# 702_MAX6675_solder_station_v1.net
KiCad netlist of a schematic drawn in EAGLE
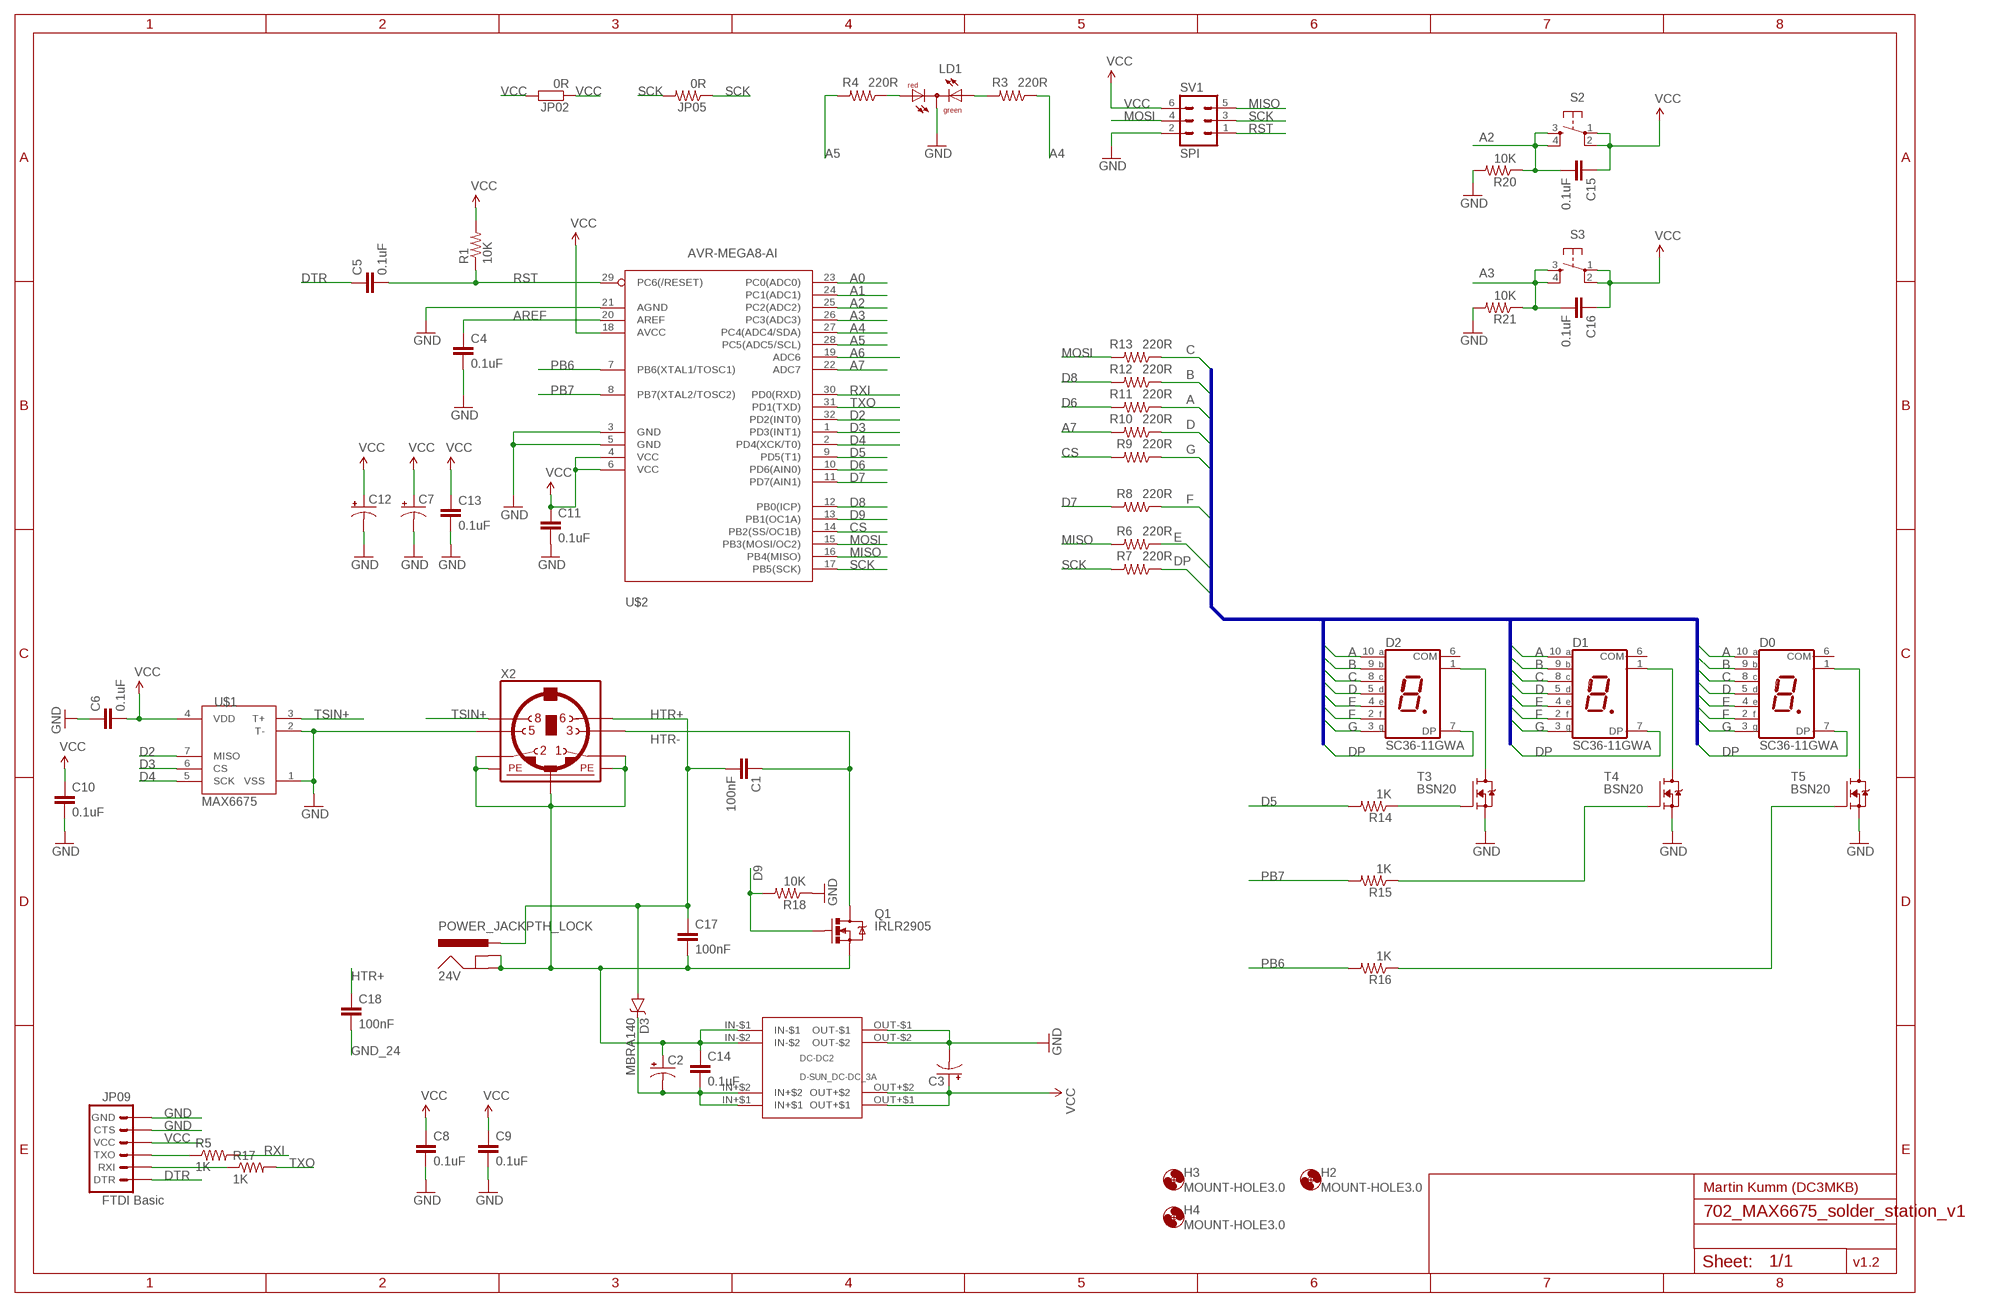
[diagram p0: schematic, sheet 1]

(export (version "E")
  (design (tool "Eeschema 10.0.6"))
  (components
    (comp (ref "24V")
      (value "POWER_JACKPTH_LOCK")
      (footprint "eagle-import:POWER_JACK_PTH_LOCK")
      (libsource (lib "eagle-import") (part "POWER_JACKPTH_LOCK"))
    )
    (comp (ref "C1")
      (value "100nF")
      (footprint "eagle-import:1206")
      (libsource (lib "eagle-import") (part "SparkFun-Passives_CAP1206"))
    )
    (comp (ref "C2")
      (value "CAP_POLPTH1")
      (footprint "eagle-import:CPOL-RADIAL-100UF-25V")
      (libsource (lib "eagle-import") (part "SparkFun-Passives_CAP_POLPTH1"))
    )
    (comp (ref "C3")
      (value "CAP_POLPTH1")
      (footprint "eagle-import:CPOL-RADIAL-100UF-25V")
      (libsource (lib "eagle-import") (part "SparkFun-Passives_CAP_POLPTH1"))
    )
    (comp (ref "C4")
      (value "0.1uF")
      (footprint "eagle-import:0805")
      (libsource (lib "eagle-import") (part "CAP0805"))
    )
    (comp (ref "C5")
      (value "0.1uF")
      (footprint "eagle-import:0805")
      (libsource (lib "eagle-import") (part "CAP0805"))
    )
    (comp (ref "C6")
      (value "0.1uF")
      (footprint "eagle-import:0805")
      (libsource (lib "eagle-import") (part "CAP0805"))
    )
    (comp (ref "C7")
      (value "CAP_POL1206")
      (footprint "eagle-import:EIA3216")
      (libsource (lib "eagle-import") (part "CAP_POL1206"))
    )
    (comp (ref "C8")
      (value "0.1uF")
      (footprint "eagle-import:0805")
      (libsource (lib "eagle-import") (part "CAP0805"))
    )
    (comp (ref "C9")
      (value "0.1uF")
      (footprint "eagle-import:0805")
      (libsource (lib "eagle-import") (part "CAP0805"))
    )
    (comp (ref "C10")
      (value "0.1uF")
      (footprint "eagle-import:0805")
      (libsource (lib "eagle-import") (part "CAP0805"))
    )
    (comp (ref "C11")
      (value "0.1uF")
      (footprint "eagle-import:0805")
      (libsource (lib "eagle-import") (part "CAP0805"))
    )
    (comp (ref "C12")
      (value "CAP_POL1206")
      (footprint "eagle-import:EIA3216")
      (libsource (lib "eagle-import") (part "CAP_POL1206"))
    )
    (comp (ref "C13")
      (value "0.1uF")
      (footprint "eagle-import:0805")
      (libsource (lib "eagle-import") (part "CAP0805"))
    )
    (comp (ref "C14")
      (value "0.1uF")
      (footprint "eagle-import:1206")
      (libsource (lib "eagle-import") (part "CAP1206"))
    )
    (comp (ref "C15")
      (value "0.1uF")
      (footprint "eagle-import:0805")
      (libsource (lib "eagle-import") (part "CAP0805"))
    )
    (comp (ref "C16")
      (value "0.1uF")
      (footprint "eagle-import:0805")
      (libsource (lib "eagle-import") (part "CAP0805"))
    )
    (comp (ref "C17")
      (value "100nF")
      (footprint "eagle-import:1206")
      (libsource (lib "eagle-import") (part "SparkFun-Passives_CAP1206"))
    )
    (comp (ref "C18")
      (value "100nF")
      (footprint "eagle-import:1206")
      (libsource (lib "eagle-import") (part "SparkFun-Passives_CAP1206"))
    )
    (comp (ref "D0")
      (value "SC36-11GWA")
      (footprint "eagle-import:SA36-11GWA")
      (libsource (lib "eagle-import") (part "SA36-11GWA"))
    )
    (comp (ref "D1")
      (value "SC36-11GWA")
      (footprint "eagle-import:SA36-11GWA")
      (libsource (lib "eagle-import") (part "SA36-11GWA"))
    )
    (comp (ref "D2")
      (value "SC36-11GWA")
      (footprint "eagle-import:SA36-11GWA")
      (libsource (lib "eagle-import") (part "SA36-11GWA"))
    )
    (comp (ref "D3")
      (value "MBRA140")
      (footprint "eagle-import:SMA-DIODE")
      (libsource (lib "eagle-import") (part "MBRA140"))
    )
    (comp (ref "DC-DC2")
      (value "D-SUN_DC-DC_3A")
      (footprint "eagle-import:D-SUN_DC-DC_3A")
      (libsource (lib "eagle-import") (part "D-SUN_DC-DC_3A"))
    )
    (comp (ref "H2")
      (value "MOUNT-HOLE3.0")
      (footprint "eagle-import:3,0")
      (libsource (lib "eagle-import") (part "MOUNT-HOLE3.0"))
    )
    (comp (ref "H3")
      (value "MOUNT-HOLE3.0")
      (footprint "eagle-import:3,0")
      (libsource (lib "eagle-import") (part "MOUNT-HOLE3.0"))
    )
    (comp (ref "H4")
      (value "MOUNT-HOLE3.0")
      (footprint "eagle-import:3,0")
      (libsource (lib "eagle-import") (part "MOUNT-HOLE3.0"))
    )
    (comp (ref "JP02")
      (value "0R")
      (footprint "eagle-import:R1206")
      (libsource (lib "eagle-import") (part "R-EU_R1206"))
    )
    (comp (ref "JP05")
      (value "0R")
      (footprint "eagle-import:0805")
      (libsource (lib "eagle-import") (part "RESISTOR0805-RES"))
    )
    (comp (ref "JP09")
      (value "FTDI Basic")
      (footprint "eagle-import:1X06")
      (libsource (lib "eagle-import") (part "ARDUINO_SERIAL_PROGRAMPTH"))
    )
    (comp (ref "LD1")
      (value "DUOLED-RG-C")
      (footprint "eagle-import:DUOLED-C-5MM")
      (libsource (lib "eagle-import") (part "DUOLED-RG-C"))
    )
    (comp (ref "Q1")
      (value "IRLR2905")
      (footprint "eagle-import:DPAK")
      (libsource (lib "eagle-import") (part "MOSFET-NCHANNELFDD8780"))
    )
    (comp (ref "R1")
      (value "10K")
      (footprint "eagle-import:0805")
      (libsource (lib "eagle-import") (part "RESISTOR0805-RES"))
    )
    (comp (ref "R3")
      (value "220R")
      (footprint "eagle-import:0805")
      (libsource (lib "eagle-import") (part "RESISTOR0805-RES"))
    )
    (comp (ref "R4")
      (value "220R")
      (footprint "eagle-import:0805")
      (libsource (lib "eagle-import") (part "RESISTOR0805-RES"))
    )
    (comp (ref "R5")
      (value "1K")
      (footprint "eagle-import:0805")
      (libsource (lib "eagle-import") (part "RESISTOR0805-RES"))
    )
    (comp (ref "R6")
      (value "220R")
      (footprint "eagle-import:0805")
      (libsource (lib "eagle-import") (part "RESISTOR0805-RES"))
    )
    (comp (ref "R7")
      (value "220R")
      (footprint "eagle-import:0805")
      (libsource (lib "eagle-import") (part "RESISTOR0805-RES"))
    )
    (comp (ref "R8")
      (value "220R")
      (footprint "eagle-import:0805")
      (libsource (lib "eagle-import") (part "RESISTOR0805-RES"))
    )
    (comp (ref "R9")
      (value "220R")
      (footprint "eagle-import:0805")
      (libsource (lib "eagle-import") (part "RESISTOR0805-RES"))
    )
    (comp (ref "R10")
      (value "220R")
      (footprint "eagle-import:0805")
      (libsource (lib "eagle-import") (part "RESISTOR0805-RES"))
    )
    (comp (ref "R11")
      (value "220R")
      (footprint "eagle-import:0805")
      (libsource (lib "eagle-import") (part "RESISTOR0805-RES"))
    )
    (comp (ref "R12")
      (value "220R")
      (footprint "eagle-import:0805")
      (libsource (lib "eagle-import") (part "RESISTOR0805-RES"))
    )
    (comp (ref "R13")
      (value "220R")
      (footprint "eagle-import:0805")
      (libsource (lib "eagle-import") (part "RESISTOR0805-RES"))
    )
    (comp (ref "R14")
      (value "1K")
      (footprint "eagle-import:0805")
      (libsource (lib "eagle-import") (part "RESISTOR0805-RES"))
    )
    (comp (ref "R15")
      (value "1K")
      (footprint "eagle-import:0805")
      (libsource (lib "eagle-import") (part "RESISTOR0805-RES"))
    )
    (comp (ref "R16")
      (value "1K")
      (footprint "eagle-import:0805")
      (libsource (lib "eagle-import") (part "RESISTOR0805-RES"))
    )
    (comp (ref "R17")
      (value "1K")
      (footprint "eagle-import:0805")
      (libsource (lib "eagle-import") (part "RESISTOR0805-RES"))
    )
    (comp (ref "R18")
      (value "10K")
      (footprint "eagle-import:0805")
      (libsource (lib "eagle-import") (part "RESISTOR0805-RES"))
    )
    (comp (ref "R20")
      (value "10K")
      (footprint "eagle-import:0805")
      (libsource (lib "eagle-import") (part "RESISTOR0805-RES"))
    )
    (comp (ref "R21")
      (value "10K")
      (footprint "eagle-import:0805")
      (libsource (lib "eagle-import") (part "RESISTOR0805-RES"))
    )
    (comp (ref "S2")
      (value "TAC_SWITCHPTH")
      (footprint "eagle-import:TACTILE-PTH")
      (libsource (lib "eagle-import") (part "TAC_SWITCHPTH"))
    )
    (comp (ref "S3")
      (value "TAC_SWITCHPTH")
      (footprint "eagle-import:TACTILE-PTH")
      (libsource (lib "eagle-import") (part "TAC_SWITCHPTH"))
    )
    (comp (ref "SV1")
      (value "SPI")
      (footprint "eagle-import:ML6")
      (libsource (lib "eagle-import") (part "ML6"))
    )
    (comp (ref "T3")
      (value "BSN20")
      (footprint "eagle-import:SOT23")
      (libsource (lib "eagle-import") (part "BSN20"))
    )
    (comp (ref "T4")
      (value "BSN20")
      (footprint "eagle-import:SOT23")
      (libsource (lib "eagle-import") (part "BSN20"))
    )
    (comp (ref "T5")
      (value "BSN20")
      (footprint "eagle-import:SOT23")
      (libsource (lib "eagle-import") (part "BSN20"))
    )
    (comp (ref "U$1")
      (value "MAX6675")
      (footprint "eagle-import:SO08-MAX6675")
      (libsource (lib "eagle-import") (part "MAX6675"))
    )
    (comp (ref "U$2")
      (value "AVR-MEGA8-AI")
      (footprint "eagle-import:TQFP32-08")
      (libsource (lib "eagle-import") (part "AVR-MEGA8-AI"))
    )
    (comp (ref "X2")
      (value "MINI_DIN_6")
      (footprint "eagle-import:M_DIN6")
      (libsource (lib "eagle-import") (part "MINI_DIN_6"))
    )
  )
  (nets
    (net (code "1") (name "/A") (class "Default")
      (node (ref "D0") (pin "10") (pinfunction "A_10") (pintype "passive"))
      (node (ref "D1") (pin "10") (pinfunction "A_10") (pintype "passive"))
      (node (ref "D2") (pin "10") (pinfunction "A_10") (pintype "passive"))
      (node (ref "R11") (pin "1") (pinfunction "1_1") (pintype "passive"))
    )
    (net (code "2") (name "/A0") (class "Default")
      (node (ref "U$2") (pin "23") (pinfunction "PC0(ADC0)_23") (pintype "bidirectional"))
    )
    (net (code "3") (name "/A1") (class "Default")
      (node (ref "U$2") (pin "24") (pinfunction "PC1(ADC1)_24") (pintype "bidirectional"))
    )
    (net (code "4") (name "/A2") (class "Default")
      (node (ref "C15") (pin "2") (pinfunction "2_2") (pintype "passive"))
      (node (ref "R20") (pin "1") (pinfunction "1_1") (pintype "passive"))
      (node (ref "S2") (pin "3") (pinfunction "3_3") (pintype "passive"))
      (node (ref "S2") (pin "4") (pinfunction "4_4") (pintype "passive"))
      (node (ref "U$2") (pin "25") (pinfunction "PC2(ADC2)_25") (pintype "bidirectional"))
    )
    (net (code "5") (name "/A3") (class "Default")
      (node (ref "C16") (pin "2") (pinfunction "2_2") (pintype "passive"))
      (node (ref "R21") (pin "1") (pinfunction "1_1") (pintype "passive"))
      (node (ref "S3") (pin "3") (pinfunction "3_3") (pintype "passive"))
      (node (ref "S3") (pin "4") (pinfunction "4_4") (pintype "passive"))
      (node (ref "U$2") (pin "26") (pinfunction "PC3(ADC3)_26") (pintype "bidirectional"))
    )
    (net (code "6") (name "/A4") (class "Default")
      (node (ref "R3") (pin "1") (pinfunction "1_1") (pintype "passive"))
      (node (ref "U$2") (pin "27") (pinfunction "PC4(ADC4/SDA)_27") (pintype "bidirectional"))
    )
    (net (code "7") (name "/A5") (class "Default")
      (node (ref "R4") (pin "2") (pinfunction "2_2") (pintype "passive"))
      (node (ref "U$2") (pin "28") (pinfunction "PC5(ADC5/SCL)_28") (pintype "bidirectional"))
    )
    (net (code "8") (name "/A6") (class "Default")
      (node (ref "U$2") (pin "19") (pinfunction "ADC6_19") (pintype "bidirectional"))
    )
    (net (code "9") (name "/A7") (class "Default")
      (node (ref "R10") (pin "2") (pinfunction "2_2") (pintype "passive"))
      (node (ref "U$2") (pin "22") (pinfunction "ADC7_22") (pintype "bidirectional"))
    )
    (net (code "10") (name "/AREF") (class "Default")
      (node (ref "C4") (pin "1") (pinfunction "1_1") (pintype "passive"))
      (node (ref "U$2") (pin "20") (pinfunction "AREF_20") (pintype "bidirectional"))
    )
    (net (code "11") (name "/B") (class "Default")
      (node (ref "D0") (pin "9") (pinfunction "B_9") (pintype "passive"))
      (node (ref "D1") (pin "9") (pinfunction "B_9") (pintype "passive"))
      (node (ref "D2") (pin "9") (pinfunction "B_9") (pintype "passive"))
      (node (ref "R12") (pin "1") (pinfunction "1_1") (pintype "passive"))
    )
    (net (code "12") (name "/C") (class "Default")
      (node (ref "D0") (pin "8") (pinfunction "C_8") (pintype "passive"))
      (node (ref "D1") (pin "8") (pinfunction "C_8") (pintype "passive"))
      (node (ref "D2") (pin "8") (pinfunction "C_8") (pintype "passive"))
      (node (ref "R13") (pin "1") (pinfunction "1_1") (pintype "passive"))
    )
    (net (code "13") (name "/CS") (class "Default")
      (node (ref "R9") (pin "2") (pinfunction "2_2") (pintype "passive"))
      (node (ref "U$2") (pin "14") (pinfunction "PB2(SS/OC1B)_14") (pintype "bidirectional"))
    )
    (net (code "14") (name "/D") (class "Default")
      (node (ref "D0") (pin "5") (pinfunction "D_5") (pintype "passive"))
      (node (ref "D1") (pin "5") (pinfunction "D_5") (pintype "passive"))
      (node (ref "D2") (pin "5") (pinfunction "D_5") (pintype "passive"))
      (node (ref "R10") (pin "1") (pinfunction "1_1") (pintype "passive"))
    )
    (net (code "15") (name "/D2") (class "Default")
      (node (ref "U$1") (pin "7") (pinfunction "MISO_7") (pintype "bidirectional"))
      (node (ref "U$2") (pin "32") (pinfunction "PD2(INT0)_32") (pintype "bidirectional"))
    )
    (net (code "16") (name "/D3") (class "Default")
      (node (ref "U$1") (pin "6") (pinfunction "CS_6") (pintype "bidirectional"))
      (node (ref "U$2") (pin "1") (pinfunction "PD3(INT1)_1") (pintype "bidirectional"))
    )
    (net (code "17") (name "/D4") (class "Default")
      (node (ref "U$1") (pin "5") (pinfunction "SCK_5") (pintype "bidirectional"))
      (node (ref "U$2") (pin "2") (pinfunction "PD4(XCK/T0)_2") (pintype "bidirectional"))
    )
    (net (code "18") (name "/D5") (class "Default")
      (node (ref "R14") (pin "2") (pinfunction "2_2") (pintype "passive"))
      (node (ref "U$2") (pin "9") (pinfunction "PD5(T1)_9") (pintype "bidirectional"))
    )
    (net (code "19") (name "/D6") (class "Default")
      (node (ref "R11") (pin "2") (pinfunction "2_2") (pintype "passive"))
      (node (ref "U$2") (pin "10") (pinfunction "PD6(AIN0)_10") (pintype "bidirectional"))
    )
    (net (code "20") (name "/D7") (class "Default")
      (node (ref "R8") (pin "2") (pinfunction "2_2") (pintype "passive"))
      (node (ref "U$2") (pin "11") (pinfunction "PD7(AIN1)_11") (pintype "bidirectional"))
    )
    (net (code "21") (name "/D8") (class "Default")
      (node (ref "R12") (pin "2") (pinfunction "2_2") (pintype "passive"))
      (node (ref "U$2") (pin "12") (pinfunction "PB0(ICP)_12") (pintype "bidirectional"))
    )
    (net (code "22") (name "/D9") (class "Default")
      (node (ref "Q1") (pin "1") (pinfunction "G_1") (pintype "passive"))
      (node (ref "R18") (pin "2") (pinfunction "2_2") (pintype "passive"))
      (node (ref "U$2") (pin "13") (pinfunction "PB1(OC1A)_13") (pintype "bidirectional"))
    )
    (net (code "23") (name "/DP") (class "Default")
      (node (ref "D0") (pin "7") (pinfunction "DP_7") (pintype "passive"))
      (node (ref "D1") (pin "7") (pinfunction "DP_7") (pintype "passive"))
      (node (ref "D2") (pin "7") (pinfunction "DP_7") (pintype "passive"))
      (node (ref "R7") (pin "1") (pinfunction "1_1") (pintype "passive"))
    )
    (net (code "24") (name "/DTR") (class "Default")
      (node (ref "C5") (pin "1") (pinfunction "1_1") (pintype "passive"))
      (node (ref "JP09") (pin "1") (pinfunction "DTR_1") (pintype "passive"))
    )
    (net (code "25") (name "/E") (class "Default")
      (node (ref "D0") (pin "4") (pinfunction "E_4") (pintype "passive"))
      (node (ref "D1") (pin "4") (pinfunction "E_4") (pintype "passive"))
      (node (ref "D2") (pin "4") (pinfunction "E_4") (pintype "passive"))
      (node (ref "R6") (pin "1") (pinfunction "1_1") (pintype "passive"))
    )
    (net (code "26") (name "/F") (class "Default")
      (node (ref "D0") (pin "2") (pinfunction "F_2") (pintype "passive"))
      (node (ref "D1") (pin "2") (pinfunction "F_2") (pintype "passive"))
      (node (ref "D2") (pin "2") (pinfunction "F_2") (pintype "passive"))
      (node (ref "R8") (pin "1") (pinfunction "1_1") (pintype "passive"))
    )
    (net (code "27") (name "/G") (class "Default")
      (node (ref "D0") (pin "3") (pinfunction "G_3") (pintype "passive"))
      (node (ref "D1") (pin "3") (pinfunction "G_3") (pintype "passive"))
      (node (ref "D2") (pin "3") (pinfunction "G_3") (pintype "passive"))
      (node (ref "R9") (pin "1") (pinfunction "1_1") (pintype "passive"))
    )
    (net (code "28") (name "/GND_24") (class "Default")
      (node (ref "24V") (pin "GND") (pinfunction "GND_GND") (pintype "bidirectional"))
      (node (ref "24V") (pin "GNDBREAK") (pinfunction "GNDBREAK_GNDBREAK") (pintype "bidirectional"))
      (node (ref "C14") (pin "1") (pinfunction "1_1") (pintype "passive"))
      (node (ref "C17") (pin "2") (pinfunction "2_2") (pintype "passive"))
      (node (ref "C18") (pin "2") (pinfunction "2_2") (pintype "passive"))
      (node (ref "C2") (pin "1") (pinfunction "+_1") (pintype "passive"))
      (node (ref "DC-DC2") (pin "IN-$1") (pinfunction "IN-$1_IN-$1") (pintype "power_in"))
      (node (ref "DC-DC2") (pin "IN-$2") (pinfunction "IN-$2_IN-$2") (pintype "power_in"))
      (node (ref "Q1") (pin "3") (pinfunction "S_3") (pintype "passive"))
      (node (ref "X2") (pin "1") (pinfunction "1_1") (pintype "passive"))
      (node (ref "X2") (pin "2") (pinfunction "2_2") (pintype "passive"))
      (node (ref "X2") (pin "SH1") (pinfunction "PE1_SH1") (pintype "power_in"))
      (node (ref "X2") (pin "SH2") (pinfunction "PE2_SH2") (pintype "power_in"))
      (node (ref "X2") (pin "SH3") (pinfunction "PE3_SH3") (pintype "power_in"))
    )
    (net (code "29") (name "/HTR+") (class "Default")
      (node (ref "24V") (pin "PWR") (pinfunction "PWR_PWR") (pintype "bidirectional"))
      (node (ref "C1") (pin "2") (pinfunction "2_2") (pintype "passive"))
      (node (ref "C17") (pin "1") (pinfunction "1_1") (pintype "passive"))
      (node (ref "C18") (pin "1") (pinfunction "1_1") (pintype "passive"))
      (node (ref "D3") (pin "A") (pinfunction "A_A") (pintype "passive"))
      (node (ref "X2") (pin "6") (pinfunction "6_6") (pintype "passive"))
    )
    (net (code "30") (name "/HTR-") (class "Default")
      (node (ref "C1") (pin "1") (pinfunction "1_1") (pintype "passive"))
      (node (ref "Q1") (pin "4") (pinfunction "D_4") (pintype "passive"))
      (node (ref "X2") (pin "3") (pinfunction "3_3") (pintype "passive"))
    )
    (net (code "31") (name "/MISO") (class "Default")
      (node (ref "R6") (pin "2") (pinfunction "2_2") (pintype "passive"))
      (node (ref "SV1") (pin "5") (pinfunction "5_5") (pintype "passive"))
      (node (ref "U$2") (pin "16") (pinfunction "PB4(MISO)_16") (pintype "bidirectional"))
    )
    (net (code "32") (name "/MOSI") (class "Default")
      (node (ref "R13") (pin "2") (pinfunction "2_2") (pintype "passive"))
      (node (ref "SV1") (pin "4") (pinfunction "4_4") (pintype "passive"))
      (node (ref "U$2") (pin "15") (pinfunction "PB3(MOSI/OC2)_15") (pintype "bidirectional"))
    )
    (net (code "33") (name "/PB6") (class "Default")
      (node (ref "R16") (pin "2") (pinfunction "2_2") (pintype "passive"))
      (node (ref "U$2") (pin "7") (pinfunction "PB6(XTAL1/TOSC1)_7") (pintype "bidirectional"))
    )
    (net (code "34") (name "/PB7") (class "Default")
      (node (ref "R15") (pin "2") (pinfunction "2_2") (pintype "passive"))
      (node (ref "U$2") (pin "8") (pinfunction "PB7(XTAL2/TOSC2)_8") (pintype "bidirectional"))
    )
    (net (code "35") (name "/RST") (class "Default")
      (node (ref "C5") (pin "2") (pinfunction "2_2") (pintype "passive"))
      (node (ref "R1") (pin "1") (pinfunction "1_1") (pintype "passive"))
      (node (ref "SV1") (pin "1") (pinfunction "1_1") (pintype "passive"))
      (node (ref "U$2") (pin "29") (pinfunction "PC6(/RESET)_29") (pintype "bidirectional"))
    )
    (net (code "36") (name "/RXI") (class "Default")
      (node (ref "R5") (pin "2") (pinfunction "2_2") (pintype "passive"))
      (node (ref "U$2") (pin "30") (pinfunction "PD0(RXD)_30") (pintype "bidirectional"))
    )
    (net (code "37") (name "/SCK") (class "Default")
      (node (ref "JP05") (pin "1") (pinfunction "1_1") (pintype "passive"))
      (node (ref "JP05") (pin "2") (pinfunction "2_2") (pintype "passive"))
      (node (ref "R7") (pin "2") (pinfunction "2_2") (pintype "passive"))
      (node (ref "SV1") (pin "3") (pinfunction "3_3") (pintype "passive"))
      (node (ref "U$2") (pin "17") (pinfunction "PB5(SCK)_17") (pintype "bidirectional"))
    )
    (net (code "38") (name "/TSIN+") (class "Default")
      (node (ref "U$1") (pin "3") (pinfunction "T+_3") (pintype "bidirectional"))
      (node (ref "X2") (pin "8") (pinfunction "8_8") (pintype "passive"))
    )
    (net (code "39") (name "/TXO") (class "Default")
      (node (ref "R17") (pin "2") (pinfunction "2_2") (pintype "passive"))
      (node (ref "U$2") (pin "31") (pinfunction "PD1(TXD)_31") (pintype "bidirectional"))
    )
    (net (code "41") (name "GND") (class "Default")
      (node (ref "C10") (pin "2") (pinfunction "2_2") (pintype "passive"))
      (node (ref "C11") (pin "2") (pinfunction "2_2") (pintype "passive"))
      (node (ref "C12") (pin "C") (pinfunction "-_C") (pintype "passive"))
      (node (ref "C13") (pin "2") (pinfunction "2_2") (pintype "passive"))
      (node (ref "C3") (pin "2") (pinfunction "-_2") (pintype "passive"))
      (node (ref "C4") (pin "2") (pinfunction "2_2") (pintype "passive"))
      (node (ref "C6") (pin "1") (pinfunction "1_1") (pintype "passive"))
      (node (ref "C7") (pin "C") (pinfunction "-_C") (pintype "passive"))
      (node (ref "C8") (pin "2") (pinfunction "2_2") (pintype "passive"))
      (node (ref "C9") (pin "2") (pinfunction "2_2") (pintype "passive"))
      (node (ref "DC-DC2") (pin "OUT-$1") (pinfunction "OUT-$1_OUT-$1") (pintype "power_in"))
      (node (ref "DC-DC2") (pin "OUT-$2") (pinfunction "OUT-$2_OUT-$2") (pintype "power_in"))
      (node (ref "JP09") (pin "5") (pinfunction "CTS_5") (pintype "passive"))
      (node (ref "JP09") (pin "6") (pinfunction "GND_6") (pintype "passive"))
      (node (ref "LD1") (pin "C") (pinfunction "C_C") (pintype "passive"))
      (node (ref "R18") (pin "1") (pinfunction "1_1") (pintype "passive"))
      (node (ref "R20") (pin "2") (pinfunction "2_2") (pintype "passive"))
      (node (ref "R21") (pin "2") (pinfunction "2_2") (pintype "passive"))
      (node (ref "SV1") (pin "2") (pinfunction "2_2") (pintype "passive"))
      (node (ref "T3") (pin "2") (pinfunction "S_2") (pintype "passive"))
      (node (ref "T4") (pin "2") (pinfunction "S_2") (pintype "passive"))
      (node (ref "T5") (pin "2") (pinfunction "S_2") (pintype "passive"))
      (node (ref "U$1") (pin "1") (pinfunction "VSS_1") (pintype "bidirectional"))
      (node (ref "U$1") (pin "2") (pinfunction "T-_2") (pintype "bidirectional"))
      (node (ref "U$2") (pin "21") (pinfunction "AGND_21") (pintype "bidirectional"))
      (node (ref "U$2") (pin "3") (pinfunction "GND_3") (pintype "bidirectional"))
      (node (ref "U$2") (pin "5") (pinfunction "GND_5") (pintype "bidirectional"))
      (node (ref "X2") (pin "5") (pinfunction "5_5") (pintype "passive"))
    )
    (net (code "42") (name "Net-(C2--)") (class "Default")
      (node (ref "C14") (pin "2") (pinfunction "2_2") (pintype "passive"))
      (node (ref "C2") (pin "2") (pinfunction "-_2") (pintype "passive"))
      (node (ref "D3") (pin "C") (pinfunction "C_C") (pintype "passive"))
      (node (ref "DC-DC2") (pin "IN+$1") (pinfunction "IN+$1_IN+$1") (pintype "power_in"))
      (node (ref "DC-DC2") (pin "IN+$2") (pinfunction "IN+$2_IN+$2") (pintype "power_in"))
    )
    (net (code "43") (name "Net-(JP09-RXI)") (class "Default")
      (node (ref "JP09") (pin "2") (pinfunction "RXI_2") (pintype "passive"))
      (node (ref "R17") (pin "1") (pinfunction "1_1") (pintype "passive"))
    )
    (net (code "44") (name "Net-(JP09-TXO)") (class "Default")
      (node (ref "JP09") (pin "3") (pinfunction "TXO_3") (pintype "passive"))
      (node (ref "R5") (pin "1") (pinfunction "1_1") (pintype "passive"))
    )
    (net (code "45") (name "Net-(LD1-AG)") (class "Default")
      (node (ref "LD1") (pin "AX") (pinfunction "AG_AX") (pintype "passive"))
      (node (ref "R3") (pin "2") (pinfunction "2_2") (pintype "passive"))
    )
    (net (code "46") (name "Net-(LD1-PadAR)") (class "Default")
      (node (ref "LD1") (pin "AR") (pinfunction "AR_AR") (pintype "passive"))
      (node (ref "R4") (pin "1") (pinfunction "1_1") (pintype "passive"))
    )
    (net (code "47") (name "Net-(T3-D)") (class "Default")
      (node (ref "D2") (pin "1") (pinfunction "COM_1") (pintype "passive"))
      (node (ref "T3") (pin "3") (pinfunction "D_3") (pintype "passive"))
    )
    (net (code "48") (name "Net-(T3-G)") (class "Default")
      (node (ref "R14") (pin "1") (pinfunction "1_1") (pintype "passive"))
      (node (ref "T3") (pin "1") (pinfunction "G_1") (pintype "passive"))
    )
    (net (code "49") (name "Net-(T4-D)") (class "Default")
      (node (ref "D1") (pin "1") (pinfunction "COM_1") (pintype "passive"))
      (node (ref "T4") (pin "3") (pinfunction "D_3") (pintype "passive"))
    )
    (net (code "50") (name "Net-(T4-G)") (class "Default")
      (node (ref "R15") (pin "1") (pinfunction "1_1") (pintype "passive"))
      (node (ref "T4") (pin "1") (pinfunction "G_1") (pintype "passive"))
    )
    (net (code "51") (name "Net-(T5-D)") (class "Default")
      (node (ref "D0") (pin "1") (pinfunction "COM_1") (pintype "passive"))
      (node (ref "T5") (pin "3") (pinfunction "D_3") (pintype "passive"))
    )
    (net (code "52") (name "Net-(T5-G)") (class "Default")
      (node (ref "R16") (pin "1") (pinfunction "1_1") (pintype "passive"))
      (node (ref "T5") (pin "1") (pinfunction "G_1") (pintype "passive"))
    )
    (net (code "53") (name "VCC") (class "Default")
      (node (ref "C10") (pin "1") (pinfunction "1_1") (pintype "passive"))
      (node (ref "C11") (pin "1") (pinfunction "1_1") (pintype "passive"))
      (node (ref "C12") (pin "A") (pinfunction "+_A") (pintype "passive"))
      (node (ref "C13") (pin "1") (pinfunction "1_1") (pintype "passive"))
      (node (ref "C15") (pin "1") (pinfunction "1_1") (pintype "passive"))
      (node (ref "C16") (pin "1") (pinfunction "1_1") (pintype "passive"))
      (node (ref "C3") (pin "1") (pinfunction "+_1") (pintype "passive"))
      (node (ref "C6") (pin "2") (pinfunction "2_2") (pintype "passive"))
      (node (ref "C7") (pin "A") (pinfunction "+_A") (pintype "passive"))
      (node (ref "C8") (pin "1") (pinfunction "1_1") (pintype "passive"))
      (node (ref "C9") (pin "1") (pinfunction "1_1") (pintype "passive"))
      (node (ref "DC-DC2") (pin "OUT+$1") (pinfunction "OUT+$1_OUT+$1") (pintype "power_in"))
      (node (ref "DC-DC2") (pin "OUT+$2") (pinfunction "OUT+$2_OUT+$2") (pintype "power_in"))
      (node (ref "JP02") (pin "1") (pinfunction "1_1") (pintype "passive"))
      (node (ref "JP02") (pin "2") (pinfunction "2_2") (pintype "passive"))
      (node (ref "JP09") (pin "4") (pinfunction "VCC_4") (pintype "passive"))
      (node (ref "R1") (pin "2") (pinfunction "2_2") (pintype "passive"))
      (node (ref "S2") (pin "1") (pinfunction "1_1") (pintype "passive"))
      (node (ref "S2") (pin "2") (pinfunction "2_2") (pintype "passive"))
      (node (ref "S3") (pin "1") (pinfunction "1_1") (pintype "passive"))
      (node (ref "S3") (pin "2") (pinfunction "2_2") (pintype "passive"))
      (node (ref "SV1") (pin "6") (pinfunction "6_6") (pintype "passive"))
      (node (ref "U$1") (pin "4") (pinfunction "VDD_4") (pintype "bidirectional"))
      (node (ref "U$2") (pin "18") (pinfunction "AVCC_18") (pintype "bidirectional"))
      (node (ref "U$2") (pin "4") (pinfunction "VCC_4") (pintype "bidirectional"))
      (node (ref "U$2") (pin "6") (pinfunction "VCC_6") (pintype "bidirectional"))
    )
    (net (code "54") (name "unconnected-(D0-COM-Pad6)") (class "Default")
      (node (ref "D0") (pin "6") (pinfunction "COM_6") (pintype "passive"))
    )
    (net (code "55") (name "unconnected-(D1-COM-Pad6)") (class "Default")
      (node (ref "D1") (pin "6") (pinfunction "COM_6") (pintype "passive"))
    )
    (net (code "56") (name "unconnected-(D2-COM-Pad6)") (class "Default")
      (node (ref "D2") (pin "6") (pinfunction "COM_6") (pintype "passive"))
    )
  )
)
